# Connector-side-1.net
KiCad netlist of a schematic drawn in Altium Designer
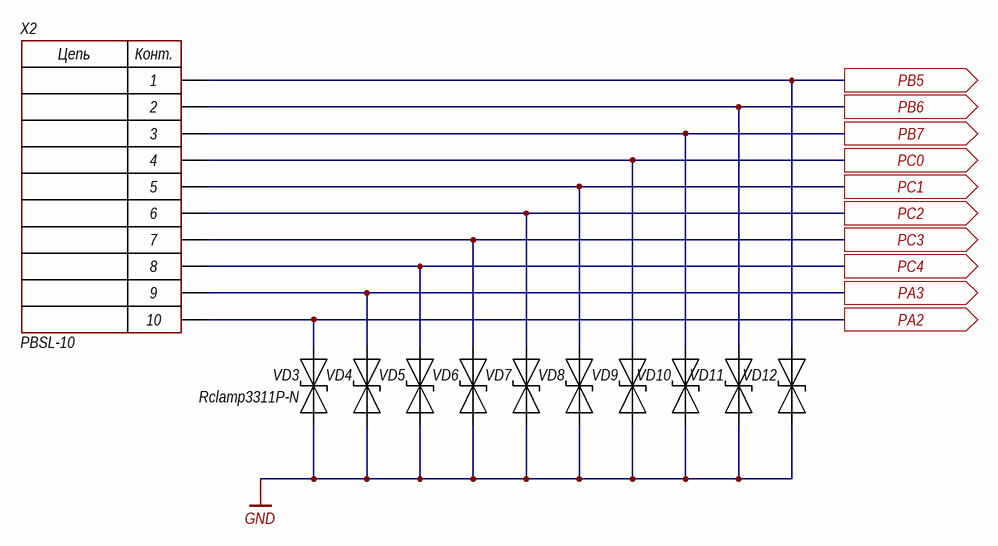
[diagram p0: Connector-side-1.SchDoc]

(export (version "E")
  (design (tool "Eeschema 10.0.6"))
  (components
    (comp (ref "VD3")
      (value "Rclamp3311P-N")
      (footprint "DFN1006-2")
      (fields (field (name "MANUFACTURER") "BORN"))
      (libsource (lib "Diods") (part "TVS-diod"))
    )
    (comp (ref "VD4")
      (value "Rclamp3311P-N")
      (footprint "DFN1006-2")
      (fields (field (name "MANUFACTURER") "BORN"))
      (libsource (lib "Diods") (part "TVS-diod"))
    )
    (comp (ref "VD5")
      (value "Rclamp3311P-N")
      (footprint "DFN1006-2")
      (fields (field (name "MANUFACTURER") "BORN"))
      (libsource (lib "Diods") (part "TVS-diod"))
    )
    (comp (ref "VD6")
      (value "Rclamp3311P-N")
      (footprint "DFN1006-2")
      (fields (field (name "MANUFACTURER") "BORN"))
      (libsource (lib "Diods") (part "TVS-diod"))
    )
    (comp (ref "VD7")
      (value "Rclamp3311P-N")
      (footprint "DFN1006-2")
      (fields (field (name "MANUFACTURER") "BORN"))
      (libsource (lib "Diods") (part "TVS-diod"))
    )
    (comp (ref "VD8")
      (value "Rclamp3311P-N")
      (footprint "DFN1006-2")
      (fields (field (name "MANUFACTURER") "BORN"))
      (libsource (lib "Diods") (part "TVS-diod"))
    )
    (comp (ref "VD9")
      (value "Rclamp3311P-N")
      (footprint "DFN1006-2")
      (fields (field (name "MANUFACTURER") "BORN"))
      (libsource (lib "Diods") (part "TVS-diod"))
    )
    (comp (ref "VD10")
      (value "Rclamp3311P-N")
      (footprint "DFN1006-2")
      (fields (field (name "MANUFACTURER") "BORN"))
      (libsource (lib "Diods") (part "TVS-diod"))
    )
    (comp (ref "VD11")
      (value "Rclamp3311P-N")
      (footprint "DFN1006-2")
      (fields (field (name "MANUFACTURER") "BORN"))
      (libsource (lib "Diods") (part "TVS-diod"))
    )
    (comp (ref "VD12")
      (value "Rclamp3311P-N")
      (footprint "DFN1006-2")
      (fields (field (name "MANUFACTURER") "BORN"))
      (libsource (lib "Diods") (part "TVS-diod"))
    )
    (comp (ref "X2")
      (value "PBSL-10")
      (footprint "CON: PBSL-10")
      (libsource (lib "Connectors") (part "10-Connector"))
    )
  )
  (nets
    (net (code "1") (name "/PA2") (class "Default")
      (node (ref "VD3") (pin "2") (pinfunction "C_2") (pintype "passive"))
      (node (ref "X2") (pin "10") (pinfunction "10_10") (pintype "passive"))
    )
    (net (code "2") (name "/PA3") (class "Default")
      (node (ref "VD4") (pin "2") (pinfunction "C_2") (pintype "passive"))
      (node (ref "X2") (pin "9") (pinfunction "9_9") (pintype "passive"))
    )
    (net (code "3") (name "/PB5") (class "Default")
      (node (ref "VD12") (pin "2") (pinfunction "C_2") (pintype "passive"))
      (node (ref "X2") (pin "1") (pinfunction "1_1") (pintype "passive"))
    )
    (net (code "4") (name "/PB6") (class "Default")
      (node (ref "VD11") (pin "2") (pinfunction "C_2") (pintype "passive"))
      (node (ref "X2") (pin "2") (pinfunction "2_2") (pintype "passive"))
    )
    (net (code "5") (name "/PB7") (class "Default")
      (node (ref "VD10") (pin "2") (pinfunction "C_2") (pintype "passive"))
      (node (ref "X2") (pin "3") (pinfunction "3_3") (pintype "passive"))
    )
    (net (code "6") (name "/PC0") (class "Default")
      (node (ref "VD9") (pin "2") (pinfunction "C_2") (pintype "passive"))
      (node (ref "X2") (pin "4") (pinfunction "4_4") (pintype "passive"))
    )
    (net (code "7") (name "/PC1") (class "Default")
      (node (ref "VD8") (pin "2") (pinfunction "C_2") (pintype "passive"))
      (node (ref "X2") (pin "5") (pinfunction "5_5") (pintype "passive"))
    )
    (net (code "8") (name "/PC2") (class "Default")
      (node (ref "VD7") (pin "2") (pinfunction "C_2") (pintype "passive"))
      (node (ref "X2") (pin "6") (pinfunction "6_6") (pintype "passive"))
    )
    (net (code "9") (name "/PC3") (class "Default")
      (node (ref "VD6") (pin "2") (pinfunction "C_2") (pintype "passive"))
      (node (ref "X2") (pin "7") (pinfunction "7_7") (pintype "passive"))
    )
    (net (code "10") (name "/PC4") (class "Default")
      (node (ref "VD5") (pin "2") (pinfunction "C_2") (pintype "passive"))
      (node (ref "X2") (pin "8") (pinfunction "8_8") (pintype "passive"))
    )
    (net (code "11") (name "GND") (class "Default")
      (node (ref "VD10") (pin "1") (pinfunction "A_1") (pintype "passive"))
      (node (ref "VD11") (pin "1") (pinfunction "A_1") (pintype "passive"))
      (node (ref "VD12") (pin "1") (pinfunction "A_1") (pintype "passive"))
      (node (ref "VD3") (pin "1") (pinfunction "A_1") (pintype "passive"))
      (node (ref "VD4") (pin "1") (pinfunction "A_1") (pintype "passive"))
      (node (ref "VD5") (pin "1") (pinfunction "A_1") (pintype "passive"))
      (node (ref "VD6") (pin "1") (pinfunction "A_1") (pintype "passive"))
      (node (ref "VD7") (pin "1") (pinfunction "A_1") (pintype "passive"))
      (node (ref "VD8") (pin "1") (pinfunction "A_1") (pintype "passive"))
      (node (ref "VD9") (pin "1") (pinfunction "A_1") (pintype "passive"))
    )
  )
)
